# DVT-Discrete-1-fIX.net
KiCad netlist of a schematic drawn in Altium Designer
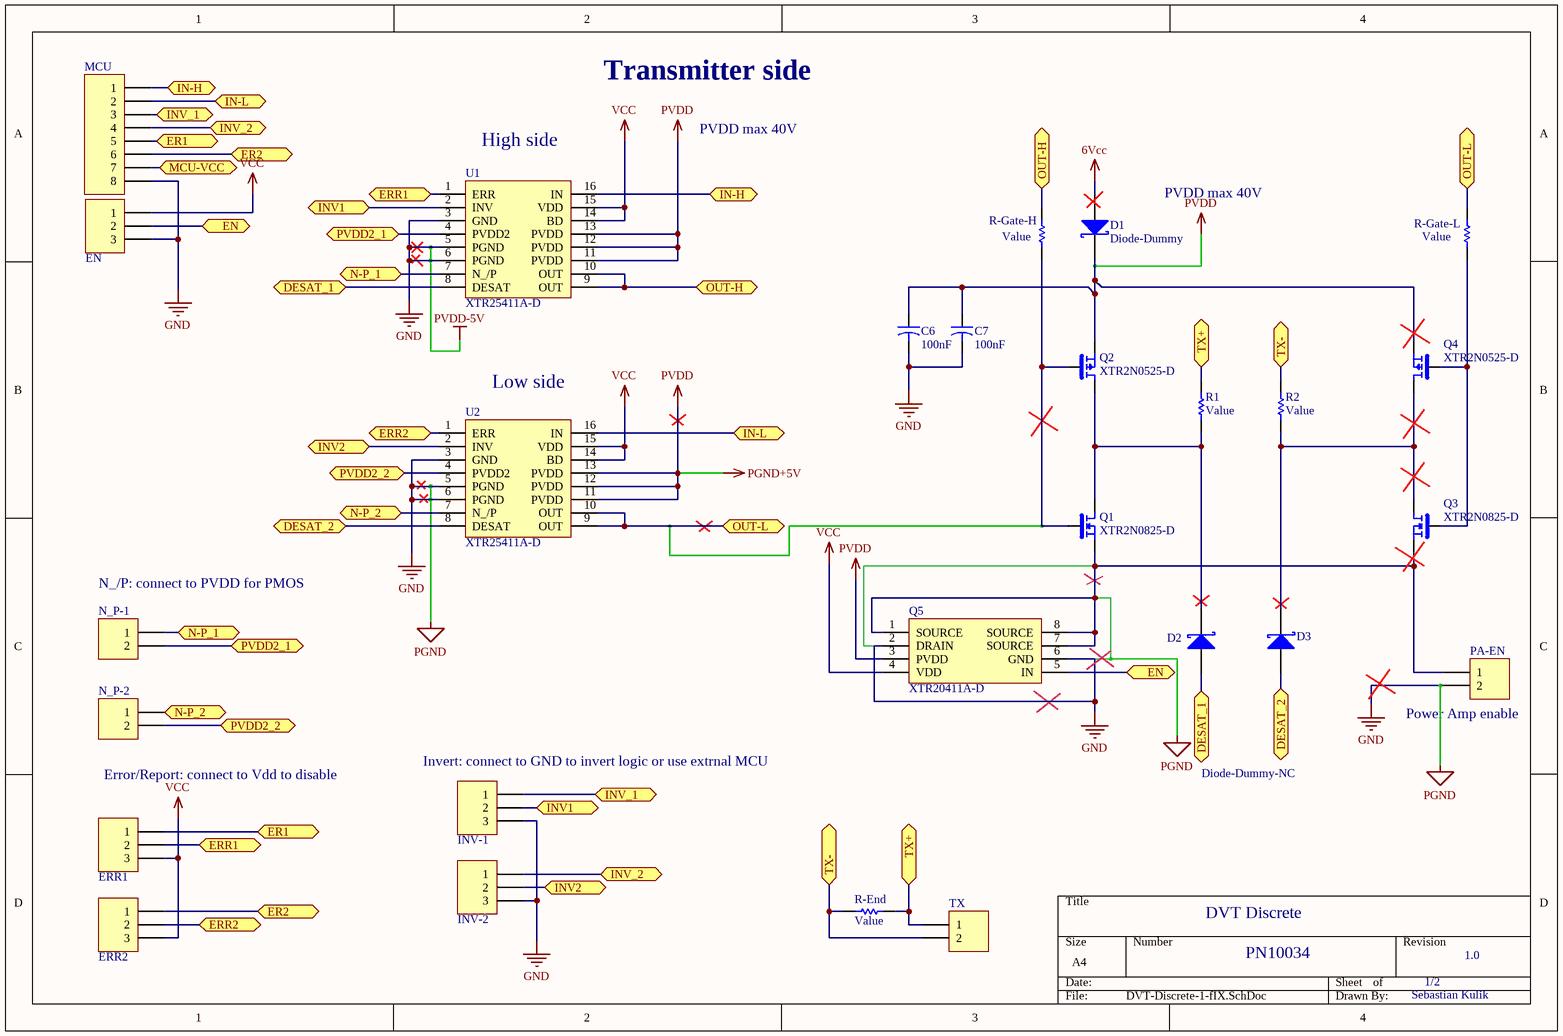
[diagram p0: DVT-Discrete-1-fIX.SchDoc]

(export (version "E")
  (design (tool "Eeschema 10.0.6"))
  (components
    (comp (ref "C6")
      (value "100nF")
      (footprint "Dummy-10mm")
      (description "Capacitor-Dummy-THT")
      (fields (field (name "MANUFACTURER") "AVX") (field (name "PUBLISHER") "Sebastian Kulik"))
      (libsource (lib "Capacitors") (part "Capacitor-Dummy-THT"))
    )
    (comp (ref "C7")
      (value "100nF")
      (footprint "Dummy-10mm")
      (description "Capacitor-Dummy-THT")
      (fields (field (name "MANUFACTURER") "AVX") (field (name "PUBLISHER") "Sebastian Kulik"))
      (libsource (lib "Capacitors") (part "Capacitor-Dummy-THT"))
    )
    (comp (ref "D1")
      (value "Diode-Dummy")
      (footprint "DO-15-Dummy")
      (fields (field (name "MANUFACTURER") "COMCHIP TECHNOLOGY") (field (name "PUBLISHER") "Sebastian Kulik"))
      (libsource (lib "Discrete") (part "Diode-Dummy"))
    )
    (comp (ref "D2")
      (value "Diode-Dummy-NC")
      (footprint "DO-15-Dummy")
      (description "Diode-Dummy")
      (fields (field (name "MANUFACTURER") "COMCHIP TECHNOLOGY") (field (name "PUBLISHER") "Sebastian Kulik"))
      (libsource (lib "Discrete") (part "Diode-Dummy"))
    )
    (comp (ref "D3")
      (value "Diode-Dummy")
      (footprint "DO-15-Dummy")
      (fields (field (name "MANUFACTURER") "COMCHIP TECHNOLOGY") (field (name "PUBLISHER") "Sebastian Kulik"))
      (libsource (lib "Discrete") (part "Diode-Dummy"))
    )
    (comp (ref "EN")
      (value "Plug_3_90_2.54")
      (footprint "HDR1X3")
      (description "Plug,-3-Pin")
      (fields (field (name "MANUFACTURER") "WE") (field (name "PUBLISHER") "Sebastian Kulik"))
      (libsource (lib "Connectors") (part "Plug_3_90_2.54"))
    )
    (comp (ref "ERR1")
      (value "Plug_3_90_2.54")
      (footprint "HDR1X3")
      (description "Plug,-3-Pin")
      (fields (field (name "MANUFACTURER") "WE") (field (name "PUBLISHER") "Sebastian Kulik"))
      (libsource (lib "Connectors") (part "Plug_3_90_2.54"))
    )
    (comp (ref "ERR2")
      (value "Plug_3_90_2.54")
      (footprint "HDR1X3")
      (description "Plug,-3-Pin")
      (fields (field (name "MANUFACTURER") "WE") (field (name "PUBLISHER") "Sebastian Kulik"))
      (libsource (lib "Connectors") (part "Plug_3_90_2.54"))
    )
    (comp (ref "INV-1")
      (value "Plug_3_90_2.54")
      (footprint "HDR1X3")
      (description "Plug,-3-Pin")
      (fields (field (name "MANUFACTURER") "WE") (field (name "PUBLISHER") "Sebastian Kulik"))
      (libsource (lib "Connectors") (part "Plug_3_90_2.54"))
    )
    (comp (ref "INV-2")
      (value "Plug_3_90_2.54")
      (footprint "HDR1X3")
      (description "Plug,-3-Pin")
      (fields (field (name "MANUFACTURER") "WE") (field (name "PUBLISHER") "Sebastian Kulik"))
      (libsource (lib "Connectors") (part "Plug_3_90_2.54"))
    )
    (comp (ref "MCU")
      (value "Plug_08_2.54")
      (footprint "HDR1X8_2.54")
      (description "Plug, 08-Pin")
      (fields (field (name "MANUFACTURER") "WE") (field (name "PUBLISHER") "Sebastian Kulik"))
      (libsource (lib "Connectors") (part "Plug_08_2.54"))
    )
    (comp (ref "N_P-1")
      (value "Plug_2_90_2.54")
      (footprint "HDR1X2")
      (description "Plug, 2-Pin")
      (fields (field (name "MANUFACTURER") "WE") (field (name "PUBLISHER") "Sebastian Kulik"))
      (libsource (lib "Connectors") (part "Plug_2_90_2.54"))
    )
    (comp (ref "N_P-2")
      (value "Plug_2_90_2.54")
      (footprint "HDR1X2")
      (description "Plug, 2-Pin")
      (fields (field (name "MANUFACTURER") "WE") (field (name "PUBLISHER") "Sebastian Kulik"))
      (libsource (lib "Connectors") (part "Plug_2_90_2.54"))
    )
    (comp (ref "PA-EN")
      (value "Plug_2_90_2.54")
      (footprint "HDR1X2")
      (description "Plug, 2-Pin")
      (fields (field (name "MANUFACTURER") "WE") (field (name "PUBLISHER") "Sebastian Kulik"))
      (libsource (lib "") (part "Plug_2_90_2.54_1"))
    )
    (comp (ref "Q1")
      (value "XTR2N0825-D")
      (footprint "DIP-8-Ceramic-HT")
      (description "N-FET, 80V@ 4A")
      (fields (field (name "MANUFACTURER") "TI") (field (name "PUBLISHER") "Sebastian Kulik"))
      (libsource (lib "Discrete") (part "XTR2N0825-D"))
    )
    (comp (ref "Q2")
      (value "XTR2N0525-D")
      (footprint "DIP-8-Ceramic-HT")
      (description "P-FET, 50V@ 4A")
      (fields (field (name "MANUFACTURER") "TI") (field (name "PUBLISHER") "Sebastian Kulik"))
      (libsource (lib "Discrete") (part "XTR2N0525-D"))
    )
    (comp (ref "Q3")
      (value "XTR2N0825-D")
      (footprint "DIP-8-Ceramic-HT")
      (description "N-FET, 80V@ 4A")
      (fields (field (name "MANUFACTURER") "TI") (field (name "PUBLISHER") "Sebastian Kulik"))
      (libsource (lib "Discrete") (part "XTR2N0825-D"))
    )
    (comp (ref "Q4")
      (value "XTR2N0525-D")
      (footprint "DIP-8-Ceramic-HT")
      (description "P-FET, 50V@ 4A")
      (fields (field (name "MANUFACTURER") "TI") (field (name "PUBLISHER") "Sebastian Kulik"))
      (libsource (lib "Discrete") (part "XTR2N0525-D"))
    )
    (comp (ref "Q5")
      (value "XTR20411A-D")
      (footprint "DIP-8-Ceramic-HT")
      (description "Gate driver")
      (fields (field (name "MANUFACTURER") "X-Rel") (field (name "PUBLISHER") "Sebastian Kulik"))
      (libsource (lib "ICs") (part "XTR20411A-D"))
    )
    (comp (ref "R-End")
      (value "Value")
      (footprint "Dummy-10mm")
      (description "Resistor-Dummy-THT")
      (fields (field (name "PUBLISHER") "Sebastian Kulik"))
      (libsource (lib "Resistors") (part "Resistor-Dummy-THT"))
    )
    (comp (ref "R-Gate-H")
      (value "Value")
      (footprint "Dummy-10mm")
      (description "Resistor-Dummy-THT")
      (fields (field (name "PUBLISHER") "Sebastian Kulik"))
      (libsource (lib "Resistors") (part "Resistor-Dummy-THT"))
    )
    (comp (ref "R-Gate-L")
      (value "Value")
      (footprint "Dummy-10mm")
      (description "Resistor-Dummy-THT")
      (fields (field (name "PUBLISHER") "Sebastian Kulik"))
      (libsource (lib "Resistors") (part "Resistor-Dummy-THT"))
    )
    (comp (ref "R1")
      (value "Value")
      (footprint "Dummy-15mm")
      (description "Resistor-Dummy-THT")
      (fields (field (name "PUBLISHER") "Sebastian Kulik"))
      (libsource (lib "Resistors") (part "Resistor-Dummy-THT"))
    )
    (comp (ref "R2")
      (value "Value")
      (footprint "Dummy-15mm")
      (description "Resistor-Dummy-THT")
      (fields (field (name "PUBLISHER") "Sebastian Kulik"))
      (libsource (lib "Resistors") (part "Resistor-Dummy-THT"))
    )
    (comp (ref "TX")
      (value "PHOENIX_1715721")
      (footprint "Phoenix-2-5_08")
      (description "Phoenix, 2 pol, 5.08mm, 22A, 715721")
      (fields (field (name "MANUFACTURER") "Phoenix") (field (name "PUBLISHER") "Sebastian Kulik"))
      (libsource (lib "Connectors") (part "2Pol_1715721"))
    )
    (comp (ref "U1")
      (value "XTR25411A-D")
      (footprint "DIP-16-Ceramic-HT")
      (description "Gate driver")
      (fields (field (name "MANUFACTURER") "X-Rel") (field (name "PUBLISHER") "Sebastian Kulik"))
      (libsource (lib "ICs") (part "XTR25411A-D"))
    )
    (comp (ref "U2")
      (value "XTR25411A-D")
      (footprint "DIP-16-Ceramic-HT")
      (description "Gate driver")
      (fields (field (name "MANUFACTURER") "X-Rel") (field (name "PUBLISHER") "Sebastian Kulik"))
      (libsource (lib "ICs") (part "XTR25411A-D"))
    )
  )
  (nets
    (net (code "1") (name "/DESAT_1") (class "Default")
      (node (ref "D2") (pin "2") (pinfunction "A_2") (pintype "passive"))
      (node (ref "U1") (pin "8") (pinfunction "DESAT_8") (pintype "passive"))
    )
    (net (code "2") (name "/DESAT_2") (class "Default")
      (node (ref "D3") (pin "2") (pinfunction "A_2") (pintype "passive"))
      (node (ref "U2") (pin "8") (pinfunction "DESAT_8") (pintype "passive"))
    )
    (net (code "3") (name "/EN") (class "Default")
      (node (ref "EN") (pin "2") (pinfunction "2_2") (pintype "passive"))
      (node (ref "Q5") (pin "5") (pinfunction "IN_5") (pintype "passive"))
    )
    (net (code "4") (name "/ER1") (class "Default")
      (node (ref "ERR1") (pin "1") (pinfunction "1_1") (pintype "passive"))
      (node (ref "MCU") (pin "5") (pinfunction "5_5") (pintype "passive"))
    )
    (net (code "5") (name "/ER2") (class "Default")
      (node (ref "ERR2") (pin "1") (pinfunction "1_1") (pintype "passive"))
      (node (ref "MCU") (pin "6") (pinfunction "6_6") (pintype "passive"))
    )
    (net (code "6") (name "/ERR1") (class "Default")
      (node (ref "ERR1") (pin "2") (pinfunction "2_2") (pintype "passive"))
      (node (ref "U1") (pin "1") (pinfunction "ERR_1") (pintype "passive"))
    )
    (net (code "7") (name "/ERR2") (class "Default")
      (node (ref "ERR2") (pin "2") (pinfunction "2_2") (pintype "passive"))
      (node (ref "U2") (pin "1") (pinfunction "ERR_1") (pintype "passive"))
    )
    (net (code "8") (name "/IN-H") (class "Default")
      (node (ref "MCU") (pin "1") (pinfunction "1_1") (pintype "passive"))
      (node (ref "U1") (pin "16") (pinfunction "IN_16") (pintype "passive"))
    )
    (net (code "9") (name "/IN-L") (class "Default")
      (node (ref "MCU") (pin "2") (pinfunction "2_2") (pintype "passive"))
      (node (ref "U2") (pin "16") (pinfunction "IN_16") (pintype "passive"))
    )
    (net (code "10") (name "/INV1") (class "Default")
      (node (ref "INV-1") (pin "2") (pinfunction "2_2") (pintype "passive"))
      (node (ref "U1") (pin "2") (pinfunction "INV_2") (pintype "passive"))
    )
    (net (code "11") (name "/INV2") (class "Default")
      (node (ref "INV-2") (pin "2") (pinfunction "2_2") (pintype "passive"))
      (node (ref "U2") (pin "2") (pinfunction "INV_2") (pintype "passive"))
    )
    (net (code "12") (name "/INV_1") (class "Default")
      (node (ref "INV-1") (pin "1") (pinfunction "1_1") (pintype "passive"))
      (node (ref "MCU") (pin "3") (pinfunction "3_3") (pintype "passive"))
    )
    (net (code "13") (name "/INV_2") (class "Default")
      (node (ref "INV-2") (pin "1") (pinfunction "1_1") (pintype "passive"))
      (node (ref "MCU") (pin "4") (pinfunction "4_4") (pintype "passive"))
    )
    (net (code "14") (name "/MCU-VCC") (class "Default")
      (node (ref "MCU") (pin "7") (pinfunction "7_7") (pintype "passive"))
    )
    (net (code "15") (name "/N-P_1") (class "Default")
      (node (ref "N_P-1") (pin "1") (pinfunction "1_1") (pintype "passive"))
      (node (ref "U1") (pin "7") (pinfunction "N_/P_7") (pintype "passive"))
    )
    (net (code "16") (name "/N-P_2") (class "Default")
      (node (ref "N_P-2") (pin "1") (pinfunction "1_1") (pintype "passive"))
      (node (ref "U2") (pin "7") (pinfunction "N_/P_7") (pintype "passive"))
    )
    (net (code "17") (name "/OUT-H") (class "Default")
      (node (ref "R-Gate-H") (pin "2") (pinfunction "2_2") (pintype "passive"))
      (node (ref "U1") (pin "10") (pinfunction "OUT_10") (pintype "passive"))
      (node (ref "U1") (pin "9") (pinfunction "OUT_9") (pintype "passive"))
    )
    (net (code "18") (name "/OUT-L") (class "Default")
      (node (ref "R-Gate-L") (pin "2") (pinfunction "2_2") (pintype "passive"))
      (node (ref "U2") (pin "10") (pinfunction "OUT_10") (pintype "passive"))
      (node (ref "U2") (pin "9") (pinfunction "OUT_9") (pintype "passive"))
    )
    (net (code "19") (name "/PVDD2_1") (class "Default")
      (node (ref "N_P-1") (pin "2") (pinfunction "2_2") (pintype "passive"))
      (node (ref "U1") (pin "4") (pinfunction "PVDD2_4") (pintype "passive"))
    )
    (net (code "20") (name "/PVDD2_2") (class "Default")
      (node (ref "N_P-2") (pin "2") (pinfunction "2_2") (pintype "passive"))
      (node (ref "U2") (pin "4") (pinfunction "PVDD2_4") (pintype "passive"))
    )
    (net (code "21") (name "/TX+") (class "Default")
      (node (ref "R-End") (pin "2") (pinfunction "2_2") (pintype "passive"))
      (node (ref "R1") (pin "2") (pinfunction "2_2") (pintype "passive"))
      (node (ref "TX") (pin "1") (pinfunction "1_1") (pintype "passive"))
    )
    (net (code "22") (name "/TX-") (class "Default")
      (node (ref "R-End") (pin "1") (pinfunction "1_1") (pintype "passive"))
      (node (ref "R2") (pin "2") (pinfunction "2_2") (pintype "passive"))
      (node (ref "TX") (pin "2") (pinfunction "2_2") (pintype "passive"))
    )
    (net (code "23") (name "6Vcc") (class "Default")
      (node (ref "D1") (pin "2") (pinfunction "A_2") (pintype "passive"))
    )
    (net (code "24") (name "GND") (class "Default")
      (node (ref "C6") (pin "2") (pinfunction "2_2") (pintype "passive"))
      (node (ref "C7") (pin "2") (pinfunction "2_2") (pintype "passive"))
      (node (ref "EN") (pin "3") (pinfunction "3_3") (pintype "passive"))
      (node (ref "INV-1") (pin "3") (pinfunction "3_3") (pintype "passive"))
      (node (ref "INV-2") (pin "3") (pinfunction "3_3") (pintype "passive"))
      (node (ref "MCU") (pin "8") (pinfunction "8_8") (pintype "passive"))
      (node (ref "PA-EN") (pin "2") (pinfunction "2_2") (pintype "passive"))
      (node (ref "Q5") (pin "2") (pinfunction "DRAIN_2") (pintype "passive"))
      (node (ref "Q5") (pin "6") (pinfunction "GND_6") (pintype "passive"))
      (node (ref "U1") (pin "3") (pinfunction "GND_3") (pintype "passive"))
      (node (ref "U1") (pin "5") (pinfunction "PGND_5") (pintype "passive"))
      (node (ref "U1") (pin "6") (pinfunction "PGND_6") (pintype "passive"))
      (node (ref "U2") (pin "3") (pinfunction "GND_3") (pintype "passive"))
      (node (ref "U2") (pin "5") (pinfunction "PGND_5") (pintype "passive"))
      (node (ref "U2") (pin "6") (pinfunction "PGND_6") (pintype "passive"))
    )
    (net (code "25") (name "Net-(D1-K)") (class "Default")
      (node (ref "C6") (pin "1") (pinfunction "1_1") (pintype "passive"))
      (node (ref "C7") (pin "1") (pinfunction "1_1") (pintype "passive"))
      (node (ref "D1") (pin "1") (pinfunction "K_1") (pintype "passive"))
      (node (ref "Q2") (pin "1") (pinfunction "Source_1") (pintype "passive"))
      (node (ref "Q4") (pin "1") (pinfunction "Source_1") (pintype "passive"))
    )
    (net (code "26") (name "Net-(D2-K)") (class "Default")
      (node (ref "D2") (pin "1") (pinfunction "K_1") (pintype "passive"))
      (node (ref "Q1") (pin "5") (pinfunction "Drain_5") (pintype "passive"))
      (node (ref "Q2") (pin "5") (pinfunction "Drain_5") (pintype "passive"))
      (node (ref "R1") (pin "1") (pinfunction "1_1") (pintype "passive"))
    )
    (net (code "27") (name "Net-(D3-K)") (class "Default")
      (node (ref "D3") (pin "1") (pinfunction "K_1") (pintype "passive"))
      (node (ref "Q3") (pin "5") (pinfunction "Drain_5") (pintype "passive"))
      (node (ref "Q4") (pin "5") (pinfunction "Drain_5") (pintype "passive"))
      (node (ref "R2") (pin "1") (pinfunction "1_1") (pintype "passive"))
    )
    (net (code "28") (name "Net-(Q1-Gate)") (class "Default")
      (node (ref "Q1") (pin "4") (pinfunction "Gate_4") (pintype "passive"))
      (node (ref "Q2") (pin "4") (pinfunction "Gate_4") (pintype "passive"))
      (node (ref "R-Gate-H") (pin "1") (pinfunction "1_1") (pintype "passive"))
    )
    (net (code "29") (name "Net-(Q1-Source)") (class "Default")
      (node (ref "PA-EN") (pin "1") (pinfunction "1_1") (pintype "passive"))
      (node (ref "Q1") (pin "1") (pinfunction "Source_1") (pintype "passive"))
      (node (ref "Q3") (pin "1") (pinfunction "Source_1") (pintype "passive"))
      (node (ref "Q5") (pin "1") (pinfunction "SOURCE_1") (pintype "passive"))
      (node (ref "Q5") (pin "7") (pinfunction "SOURCE_7") (pintype "passive"))
      (node (ref "Q5") (pin "8") (pinfunction "SOURCE_8") (pintype "passive"))
    )
    (net (code "30") (name "Net-(Q3-Gate)") (class "Default")
      (node (ref "Q3") (pin "4") (pinfunction "Gate_4") (pintype "passive"))
      (node (ref "Q4") (pin "4") (pinfunction "Gate_4") (pintype "passive"))
      (node (ref "R-Gate-L") (pin "1") (pinfunction "1_1") (pintype "passive"))
    )
    (net (code "33") (name "PVDD") (class "Default")
      (node (ref "Q5") (pin "3") (pinfunction "PVDD_3") (pintype "passive"))
      (node (ref "U1") (pin "11") (pinfunction "PVDD_11") (pintype "passive"))
      (node (ref "U1") (pin "12") (pinfunction "PVDD_12") (pintype "passive"))
      (node (ref "U1") (pin "13") (pinfunction "PVDD_13") (pintype "passive"))
      (node (ref "U2") (pin "11") (pinfunction "PVDD_11") (pintype "passive"))
      (node (ref "U2") (pin "12") (pinfunction "PVDD_12") (pintype "passive"))
      (node (ref "U2") (pin "13") (pinfunction "PVDD_13") (pintype "passive"))
    )
    (net (code "35") (name "VCC") (class "Default")
      (node (ref "EN") (pin "1") (pinfunction "1_1") (pintype "passive"))
      (node (ref "ERR1") (pin "3") (pinfunction "3_3") (pintype "passive"))
      (node (ref "ERR2") (pin "3") (pinfunction "3_3") (pintype "passive"))
      (node (ref "Q5") (pin "4") (pinfunction "VDD_4") (pintype "passive"))
      (node (ref "U1") (pin "14") (pinfunction "BD_14") (pintype "passive"))
      (node (ref "U1") (pin "15") (pinfunction "VDD_15") (pintype "passive"))
      (node (ref "U2") (pin "14") (pinfunction "BD_14") (pintype "passive"))
      (node (ref "U2") (pin "15") (pinfunction "VDD_15") (pintype "passive"))
    )
  )
)
